# SENSOR.net
KiCad netlist of a schematic drawn in Altium Designer
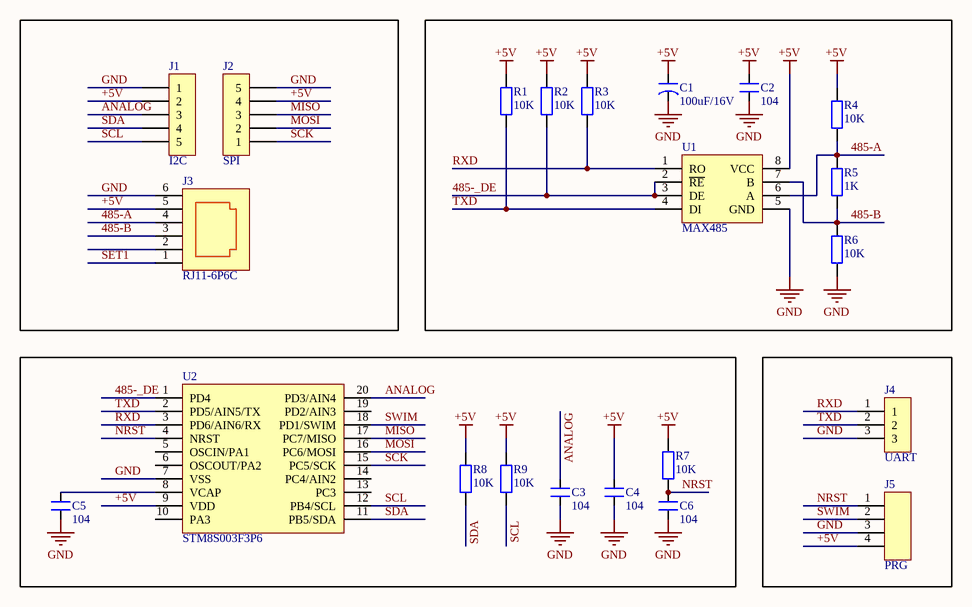
[diagram p0: SENSOR.SchDoc]

(export (version "E")
  (design (tool "Eeschema 10.0.6"))
  (components
    (comp (ref "C1")
      (value "100uF/16V")
      (footprint "CAP_AL_6.3x5.5")
      (description "Cap AL SMD")
      (libsource (lib "OAD_RD") (part "CAP_AL"))
    )
    (comp (ref "C2")
      (value "104")
      (footprint "CAP-0805")
      (description "Cap SMD")
      (libsource (lib "OAD_RD") (part "CAP"))
    )
    (comp (ref "C3")
      (value "104")
      (footprint "CAP-0805")
      (description "Cap SMD")
      (libsource (lib "OAD_RD") (part "CAP"))
    )
    (comp (ref "C4")
      (value "104")
      (footprint "CAP-0805")
      (description "Cap SMD")
      (libsource (lib "OAD_RD") (part "CAP"))
    )
    (comp (ref "C5")
      (value "104")
      (footprint "CAP-0805")
      (description "Cap SMD")
      (libsource (lib "OAD_RD") (part "CAP"))
    )
    (comp (ref "C6")
      (value "104")
      (footprint "CAP-0805")
      (description "Cap SMD")
      (libsource (lib "OAD_RD") (part "CAP"))
    )
    (comp (ref "J1")
      (value "I2C")
      (footprint "CON2 15EDG3.81-5P")
      (description "Jump_5 Pin 2.54")
      (libsource (lib "") (part "Jump_5_1"))
    )
    (comp (ref "J2")
      (value "SPI")
      (footprint "CON2 15EDG3.81-5P")
      (description "Jump_5 Pin 2.54")
      (libsource (lib "OAD_RD") (part "Jump_5"))
    )
    (comp (ref "J3")
      (value "RJ11-6P6C")
      (footprint "RJ12-6P6C")
      (description "RJ11-6P6C Connecter")
      (libsource (lib "OAD_RD") (part "RJ11-6P6C"))
    )
    (comp (ref "J4")
      (value "UART")
      (footprint "JUMP_3")
      (description "Jump_3 Pin 2.54")
      (libsource (lib "OAD_RD") (part "Jump_3"))
    )
    (comp (ref "J5")
      (value "PRG")
      (footprint "Jump_4")
      (description "Jump_4 Pin 2.54")
      (libsource (lib "OAD_RD") (part "Jump_4"))
    )
    (comp (ref "R1")
      (value "10K")
      (footprint "RES-0805")
      (description "Resistor SMD")
      (libsource (lib "OAD_RD") (part "RES"))
    )
    (comp (ref "R2")
      (value "10K")
      (footprint "RES-0805")
      (description "Resistor SMD")
      (libsource (lib "OAD_RD") (part "RES"))
    )
    (comp (ref "R3")
      (value "10K")
      (footprint "RES-0805")
      (description "Resistor SMD")
      (libsource (lib "OAD_RD") (part "RES"))
    )
    (comp (ref "R4")
      (value "10K")
      (footprint "RES-0805")
      (description "Resistor SMD")
      (libsource (lib "OAD_RD") (part "RES"))
    )
    (comp (ref "R5")
      (value "1K")
      (footprint "RES-0805")
      (description "Resistor SMD")
      (libsource (lib "OAD_RD") (part "RES"))
    )
    (comp (ref "R6")
      (value "10K")
      (footprint "RES-0805")
      (description "Resistor SMD")
      (libsource (lib "OAD_RD") (part "RES"))
    )
    (comp (ref "R7")
      (value "10K")
      (footprint "RES-0805")
      (description "Resistor SMD")
      (libsource (lib "OAD_RD") (part "RES"))
    )
    (comp (ref "R8")
      (value "10K")
      (footprint "RES-0805")
      (description "Resistor SMD")
      (libsource (lib "OAD_RD") (part "RES"))
    )
    (comp (ref "R9")
      (value "10K")
      (footprint "RES-0805")
      (description "Resistor SMD")
      (libsource (lib "OAD_RD") (part "RES"))
    )
    (comp (ref "U1")
      (value "MAX485")
      (footprint "SOP08")
      (description "RS485-Transceivers")
      (libsource (lib "OAD_RD") (part "MAX485"))
    )
    (comp (ref "U2")
      (value "STM8S003F3P6")
      (footprint "TSSOP20")
      (description "ARM")
      (libsource (lib "OAD_RD") (part "STM8S003F3P6"))
    )
  )
  (nets
    (net (code "1") (name "+5V") (class "Default")
      (node (ref "C1") (pin "1") (pinfunction "1_1") (pintype "passive"))
      (node (ref "C2") (pin "2") (pinfunction "2_2") (pintype "passive"))
      (node (ref "C4") (pin "2") (pinfunction "2_2") (pintype "passive"))
      (node (ref "J1") (pin "2") (pinfunction "2_2") (pintype "passive"))
      (node (ref "J2") (pin "4") (pinfunction "4_4") (pintype "passive"))
      (node (ref "J3") (pin "5") (pintype "passive"))
      (node (ref "J5") (pin "4") (pinfunction "4_4") (pintype "passive"))
      (node (ref "R1") (pin "2") (pinfunction "2_2") (pintype "passive"))
      (node (ref "R2") (pin "2") (pinfunction "2_2") (pintype "passive"))
      (node (ref "R3") (pin "2") (pinfunction "2_2") (pintype "passive"))
      (node (ref "R4") (pin "2") (pinfunction "2_2") (pintype "passive"))
      (node (ref "R7") (pin "2") (pinfunction "2_2") (pintype "passive"))
      (node (ref "R8") (pin "2") (pinfunction "2_2") (pintype "passive"))
      (node (ref "R9") (pin "2") (pinfunction "2_2") (pintype "passive"))
      (node (ref "U1") (pin "8") (pinfunction "VCC_8") (pintype "power_in"))
      (node (ref "U2") (pin "9") (pinfunction "VDD_9") (pintype "power_in"))
    )
    (net (code "2") (name "/485-A") (class "Default")
      (node (ref "J3") (pin "4") (pintype "passive"))
      (node (ref "R4") (pin "1") (pinfunction "1_1") (pintype "passive"))
      (node (ref "R5") (pin "2") (pinfunction "2_2") (pintype "passive"))
      (node (ref "U1") (pin "6") (pinfunction "A_6") (pintype "passive"))
    )
    (net (code "3") (name "/485-B") (class "Default")
      (node (ref "J3") (pin "3") (pintype "passive"))
      (node (ref "R5") (pin "1") (pinfunction "1_1") (pintype "passive"))
      (node (ref "R6") (pin "2") (pinfunction "2_2") (pintype "passive"))
      (node (ref "U1") (pin "7") (pinfunction "B_7") (pintype "passive"))
    )
    (net (code "4") (name "/485-_DE") (class "Default")
      (node (ref "R2") (pin "1") (pinfunction "1_1") (pintype "passive"))
      (node (ref "U1") (pin "2") (pinfunction "~{RE}_2") (pintype "passive"))
      (node (ref "U1") (pin "3") (pinfunction "DE_3") (pintype "passive"))
      (node (ref "U2") (pin "1") (pinfunction "PD4_1") (pintype "passive"))
    )
    (net (code "5") (name "/ANALOG") (class "Default")
      (node (ref "C3") (pin "2") (pinfunction "2_2") (pintype "passive"))
      (node (ref "J1") (pin "3") (pinfunction "3_3") (pintype "passive"))
      (node (ref "U2") (pin "20") (pinfunction "PD3/AIN4_20") (pintype "passive"))
    )
    (net (code "6") (name "/MISO") (class "Default")
      (node (ref "J2") (pin "3") (pinfunction "3_3") (pintype "passive"))
      (node (ref "U2") (pin "17") (pinfunction "PC7/MISO_17") (pintype "passive"))
    )
    (net (code "7") (name "/MOSI") (class "Default")
      (node (ref "J2") (pin "2") (pinfunction "2_2") (pintype "passive"))
      (node (ref "U2") (pin "16") (pinfunction "PC6/MOSI_16") (pintype "passive"))
    )
    (net (code "8") (name "/NRST") (class "Default")
      (node (ref "C6") (pin "2") (pinfunction "2_2") (pintype "passive"))
      (node (ref "J5") (pin "1") (pinfunction "1_1") (pintype "passive"))
      (node (ref "R7") (pin "1") (pinfunction "1_1") (pintype "passive"))
      (node (ref "U2") (pin "4") (pinfunction "NRST_4") (pintype "passive"))
    )
    (net (code "9") (name "/RXD") (class "Default")
      (node (ref "J4") (pin "1") (pinfunction "1_1") (pintype "passive"))
      (node (ref "R3") (pin "1") (pinfunction "1_1") (pintype "passive"))
      (node (ref "U1") (pin "1") (pinfunction "RO_1") (pintype "passive"))
      (node (ref "U2") (pin "3") (pinfunction "PD6/AIN6/RX_3") (pintype "passive"))
    )
    (net (code "10") (name "/SCK") (class "Default")
      (node (ref "J2") (pin "1") (pinfunction "1_1") (pintype "passive"))
      (node (ref "U2") (pin "15") (pinfunction "PC5/SCK_15") (pintype "passive"))
    )
    (net (code "11") (name "/SCL") (class "Default")
      (node (ref "J1") (pin "5") (pinfunction "5_5") (pintype "passive"))
      (node (ref "R9") (pin "1") (pinfunction "1_1") (pintype "passive"))
      (node (ref "U2") (pin "12") (pinfunction "PB4/SCL_12") (pintype "passive"))
    )
    (net (code "12") (name "/SDA") (class "Default")
      (node (ref "J1") (pin "4") (pinfunction "4_4") (pintype "passive"))
      (node (ref "R8") (pin "1") (pinfunction "1_1") (pintype "passive"))
      (node (ref "U2") (pin "11") (pinfunction "PB5/SDA_11") (pintype "passive"))
    )
    (net (code "13") (name "/SET1") (class "Default") (node (ref "J3") (pin "1") (pintype "passive")))
    (net (code "14") (name "/SWIM") (class "Default")
      (node (ref "J5") (pin "2") (pinfunction "2_2") (pintype "passive"))
      (node (ref "U2") (pin "18") (pinfunction "PD1/SWIM_18") (pintype "passive"))
    )
    (net (code "15") (name "/TXD") (class "Default")
      (node (ref "J4") (pin "2") (pinfunction "2_2") (pintype "passive"))
      (node (ref "R1") (pin "1") (pinfunction "1_1") (pintype "passive"))
      (node (ref "U1") (pin "4") (pinfunction "DI_4") (pintype "passive"))
      (node (ref "U2") (pin "2") (pinfunction "PD5/AIN5/TX_2") (pintype "passive"))
    )
    (net (code "16") (name "GND") (class "Default")
      (node (ref "C1") (pin "2") (pinfunction "2_2") (pintype "passive"))
      (node (ref "C2") (pin "1") (pinfunction "1_1") (pintype "passive"))
      (node (ref "C3") (pin "1") (pinfunction "1_1") (pintype "passive"))
      (node (ref "C4") (pin "1") (pinfunction "1_1") (pintype "passive"))
      (node (ref "C5") (pin "1") (pinfunction "1_1") (pintype "passive"))
      (node (ref "C6") (pin "1") (pinfunction "1_1") (pintype "passive"))
      (node (ref "J1") (pin "1") (pinfunction "1_1") (pintype "passive"))
      (node (ref "J2") (pin "5") (pinfunction "5_5") (pintype "passive"))
      (node (ref "J3") (pin "6") (pintype "passive"))
      (node (ref "J4") (pin "3") (pinfunction "3_3") (pintype "passive"))
      (node (ref "J5") (pin "3") (pinfunction "3_3") (pintype "passive"))
      (node (ref "R6") (pin "1") (pinfunction "1_1") (pintype "passive"))
      (node (ref "U1") (pin "5") (pinfunction "GND_5") (pintype "power_in"))
      (node (ref "U2") (pin "7") (pinfunction "VSS_7") (pintype "power_in"))
    )
    (net (code "17") (name "Net-(U2-VCAP)") (class "Default")
      (node (ref "C5") (pin "2") (pinfunction "2_2") (pintype "passive"))
      (node (ref "U2") (pin "8") (pinfunction "VCAP_8") (pintype "passive"))
    )
    (net (code "18") (name "unconnected-(J3-Pad2)") (class "Default")
      (node (ref "J3") (pin "2") (pintype "passive"))
    )
    (net (code "19") (name "unconnected-(U2-OSCIN{slash}PA1-Pad5)") (class "Default")
      (node (ref "U2") (pin "5") (pinfunction "OSCIN/PA1_5") (pintype "passive"))
    )
    (net (code "20") (name "unconnected-(U2-OSCOUT{slash}PA2-Pad6)") (class "Default")
      (node (ref "U2") (pin "6") (pinfunction "OSCOUT/PA2_6") (pintype "passive"))
    )
    (net (code "21") (name "unconnected-(U2-PA3-Pad10)") (class "Default")
      (node (ref "U2") (pin "10") (pinfunction "PA3_10") (pintype "passive"))
    )
    (net (code "22") (name "unconnected-(U2-PC3-Pad13)") (class "Default")
      (node (ref "U2") (pin "13") (pinfunction "PC3_13") (pintype "passive"))
    )
    (net (code "23") (name "unconnected-(U2-PC4{slash}AIN2-Pad14)") (class "Default")
      (node (ref "U2") (pin "14") (pinfunction "PC4/AIN2_14") (pintype "passive"))
    )
    (net (code "24") (name "unconnected-(U2-PD2{slash}AIN3-Pad19)") (class "Default")
      (node (ref "U2") (pin "19") (pinfunction "PD2/AIN3_19") (pintype "passive"))
    )
  )
)
